# 001_USB.net
KiCad netlist of a schematic drawn in Altium Designer
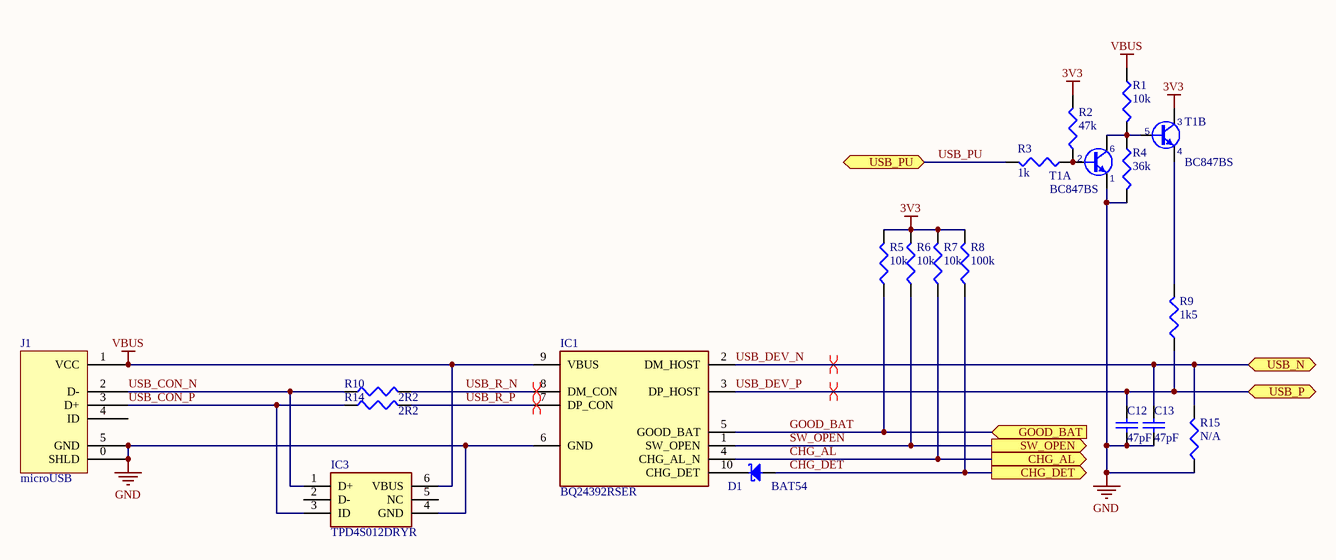
[diagram p0: [001] USB.SchDoc]

(export (version "E")
  (design (tool "Eeschema 10.0.6"))
  (components
    (comp (ref "C12")
      (value "47pF")
      (footprint "1608[0603]")
      (description "Capacitor (Semiconductor SIM Model)")
      (fields (field (name "Comment") "Cap Semi") (field (name "PUBLISHER") "Altium Limited"))
      (libsource (lib "Miscellaneous Devices") (part "Cap Semi"))
    )
    (comp (ref "C13")
      (value "47pF")
      (footprint "1608[0603]")
      (description "Capacitor (Semiconductor SIM Model)")
      (fields (field (name "Comment") "Cap Semi") (field (name "PUBLISHER") "Altium Limited"))
      (libsource (lib "Miscellaneous Devices") (part "Cap Semi"))
    )
    (comp (ref "D1")
      (value "BAT54")
      (footprint "SOT95P240X130-3N")
      (description "Diode Schottky  Anode Pin 1 Cathode Pin 3 (Pas de pin 2)")
      (fields
        (field (name "VOLTAGE") "30V")
        (field (name "POWER") "200mA")
        (field (name "AUTHOR") "CERN DEM JLC")
      )
      (libsource (lib "ICs And Semiconductors") (part "Diode Schottky A1C3"))
    )
    (comp (ref "IC1")
      (value "BQ24392RSER")
      (footprint "SamacSys:RSE(R-PUQFN-N10)")
      (description "Integrated Circuit")
      (fields (field (name "MOUSER PART NUMBER") "595-BQ24392RSER") (field (name "RS PART NUMBER") "8279327"))
      (libsource (lib "SamacSys") (part "BQ24392RSER"))
    )
    (comp (ref "IC3")
      (value "TPD4S012DRYR")
      (footprint "SamacSys:SON50P100X145X60-6N")
      (description "Integrated Circuit")
      (fields (field (name "MOUSER2 PART NUMBER") "595-TPD4S012DRYR"))
      (libsource (lib "SamacSys") (part "TPD4S012DRYR"))
    )
    (comp (ref "J1")
      (value "microUSB")
      (footprint "UB-MC5BR3-SDWP604-4S - custom")
      (description "microUSB connector")
      (libsource (lib "6DOF IMU_ver1") (part "microUSB"))
    )
    (comp (ref "R1")
      (value "10k")
      (footprint "J1-0603")
      (description "Resistor")
      (fields (field (name "Comment") "Res3") (field (name "PUBLISHER") "Altium Limited"))
      (libsource (lib "Miscellaneous Devices") (part "Res3"))
    )
    (comp (ref "R2")
      (value "47k")
      (footprint "J1-0603")
      (description "Resistor")
      (fields (field (name "Comment") "Res3") (field (name "PUBLISHER") "Altium Limited"))
      (libsource (lib "Miscellaneous Devices") (part "Res3"))
    )
    (comp (ref "R3")
      (value "1k")
      (footprint "J1-0603")
      (description "Resistor")
      (fields (field (name "Comment") "Res3") (field (name "PUBLISHER") "Altium Limited"))
      (libsource (lib "Miscellaneous Devices") (part "Res3"))
    )
    (comp (ref "R4")
      (value "36k")
      (footprint "J1-0603")
      (description "Resistor")
      (fields (field (name "Comment") "Res3") (field (name "PUBLISHER") "Altium Limited"))
      (libsource (lib "Miscellaneous Devices") (part "Res3"))
    )
    (comp (ref "R5")
      (value "10k")
      (footprint "J1-0603")
      (description "Resistor")
      (fields (field (name "Comment") "Res3") (field (name "PUBLISHER") "Altium Limited"))
      (libsource (lib "Miscellaneous Devices") (part "Res3"))
    )
    (comp (ref "R6")
      (value "10k")
      (footprint "J1-0603")
      (description "Resistor")
      (fields (field (name "Comment") "Res3") (field (name "PUBLISHER") "Altium Limited"))
      (libsource (lib "Miscellaneous Devices") (part "Res3"))
    )
    (comp (ref "R7")
      (value "10k")
      (footprint "J1-0603")
      (description "Resistor")
      (fields (field (name "Comment") "Res3") (field (name "PUBLISHER") "Altium Limited"))
      (libsource (lib "Miscellaneous Devices") (part "Res3"))
    )
    (comp (ref "R8")
      (value "100k")
      (footprint "J1-0603")
      (description "Resistor")
      (fields (field (name "Comment") "Res3") (field (name "PUBLISHER") "Altium Limited"))
      (libsource (lib "Miscellaneous Devices") (part "Res3"))
    )
    (comp (ref "R9")
      (value "1k5")
      (footprint "J1-0603")
      (description "Resistor")
      (fields (field (name "Comment") "Res3") (field (name "PUBLISHER") "Altium Limited"))
      (libsource (lib "Miscellaneous Devices") (part "Res3"))
    )
    (comp (ref "R10")
      (value "2R2")
      (footprint "J1-0603")
      (description "Resistor")
      (fields (field (name "Comment") "Res3") (field (name "PUBLISHER") "Altium Limited"))
      (libsource (lib "Miscellaneous Devices") (part "Res3"))
    )
    (comp (ref "R14")
      (value "2R2")
      (footprint "J1-0603")
      (description "Resistor")
      (fields (field (name "Comment") "Res3") (field (name "PUBLISHER") "Altium Limited"))
      (libsource (lib "Miscellaneous Devices") (part "Res3"))
    )
    (comp (ref "R15")
      (value "N/A")
      (footprint "J1-0603")
      (description "Resistor")
      (fields (field (name "Comment") "Res3") (field (name "PUBLISHER") "Altium Limited"))
      (libsource (lib "Miscellaneous Devices") (part "Res3"))
    )
    (comp (ref "T1")
      (value "BC847BS")
      (footprint "SOT65P210X110-6N")
      (description "45V 100mA Dual NPN General-Purpose Transistor")
      (fields (field (name "MANUFACTURER") "NXP SEMICONDUCTORS") (field (name "AUTHOR") "CERN DEM JMW"))
      (libsource (lib "ICs And Semiconductors") (part "BC847BS"))
    )
  )
  (nets
    (net (code "1") (name "/CHG_AL") (class "Default")
      (node (ref "IC1") (pin "4") (pinfunction "CHG_AL_N_4") (pintype "passive"))
      (node (ref "R7") (pin "1") (pinfunction "1_1") (pintype "passive"))
    )
    (net (code "2") (name "/CHG_DET") (class "Default")
      (node (ref "D1") (pin "1") (pinfunction "A_1") (pintype "passive"))
      (node (ref "R8") (pin "1") (pinfunction "1_1") (pintype "passive"))
    )
    (net (code "3") (name "/GOOD_BAT") (class "Default")
      (node (ref "IC1") (pin "5") (pinfunction "GOOD_BAT_5") (pintype "passive"))
      (node (ref "R5") (pin "1") (pinfunction "1_1") (pintype "passive"))
    )
    (net (code "4") (name "/SW_OPEN") (class "Default")
      (node (ref "IC1") (pin "1") (pinfunction "SW_OPEN_1") (pintype "passive"))
      (node (ref "R6") (pin "1") (pinfunction "1_1") (pintype "passive"))
    )
    (net (code "5") (name "/USB_CON_N") (class "Default")
      (node (ref "IC3") (pin "1") (pinfunction "D+_1") (pintype "passive"))
      (node (ref "J1") (pin "2") (pinfunction "D-_2") (pintype "passive"))
      (node (ref "R10") (pin "1") (pinfunction "1_1") (pintype "passive"))
    )
    (net (code "6") (name "/USB_CON_P") (class "Default")
      (node (ref "IC3") (pin "3") (pinfunction "ID_3") (pintype "passive"))
      (node (ref "J1") (pin "3") (pinfunction "D+_3") (pintype "passive"))
      (node (ref "R14") (pin "1") (pinfunction "1_1") (pintype "passive"))
    )
    (net (code "7") (name "/USB_DEV_N") (class "Default")
      (node (ref "C13") (pin "1") (pinfunction "1_1") (pintype "passive"))
      (node (ref "IC1") (pin "2") (pinfunction "DM_HOST_2") (pintype "passive"))
      (node (ref "R15") (pin "2") (pinfunction "2_2") (pintype "passive"))
    )
    (net (code "8") (name "/USB_DEV_P") (class "Default")
      (node (ref "C12") (pin "1") (pinfunction "1_1") (pintype "passive"))
      (node (ref "IC1") (pin "3") (pinfunction "DP_HOST_3") (pintype "passive"))
      (node (ref "R9") (pin "1") (pinfunction "1_1") (pintype "passive"))
    )
    (net (code "9") (name "/USB_PU") (class "Default")
      (node (ref "R3") (pin "2") (pinfunction "2_2") (pintype "passive"))
    )
    (net (code "10") (name "/USB_R_N") (class "Default")
      (node (ref "IC1") (pin "8") (pinfunction "DM_CON_8") (pintype "passive"))
      (node (ref "R10") (pin "2") (pinfunction "2_2") (pintype "passive"))
    )
    (net (code "11") (name "/USB_R_P") (class "Default")
      (node (ref "IC1") (pin "7") (pinfunction "DP_CON_7") (pintype "passive"))
      (node (ref "R14") (pin "2") (pinfunction "2_2") (pintype "passive"))
    )
    (net (code "12") (name "3V3") (class "Default")
      (node (ref "R2") (pin "2") (pinfunction "2_2") (pintype "passive"))
      (node (ref "R5") (pin "2") (pinfunction "2_2") (pintype "passive"))
      (node (ref "R6") (pin "2") (pinfunction "2_2") (pintype "passive"))
      (node (ref "R7") (pin "2") (pinfunction "2_2") (pintype "passive"))
      (node (ref "R8") (pin "2") (pinfunction "2_2") (pintype "passive"))
      (node (ref "T1") (pin "3") (pinfunction "C_3") (pintype "passive"))
    )
    (net (code "13") (name "GND") (class "Default")
      (node (ref "C12") (pin "2") (pinfunction "2_2") (pintype "passive"))
      (node (ref "C13") (pin "2") (pinfunction "2_2") (pintype "passive"))
      (node (ref "IC1") (pin "6") (pinfunction "GND_6") (pintype "passive"))
      (node (ref "IC3") (pin "4") (pinfunction "GND_4") (pintype "power_in"))
      (node (ref "J1") (pin "0") (pinfunction "SHLD_0") (pintype "passive"))
      (node (ref "J1") (pin "5") (pinfunction "GND_5") (pintype "power_in"))
      (node (ref "R15") (pin "1") (pinfunction "1_1") (pintype "passive"))
      (node (ref "R4") (pin "2") (pinfunction "2_2") (pintype "passive"))
      (node (ref "T1") (pin "1") (pinfunction "E_1") (pintype "passive"))
    )
    (net (code "14") (name "Net-(D1-C)") (class "Default")
      (node (ref "D1") (pin "3") (pinfunction "C_3") (pintype "passive"))
      (node (ref "IC1") (pin "10") (pinfunction "CHG_DET_10") (pintype "passive"))
    )
    (net (code "15") (name "Net-(T1A-B)") (class "Default")
      (node (ref "R2") (pin "1") (pinfunction "1_1") (pintype "passive"))
      (node (ref "R3") (pin "1") (pinfunction "1_1") (pintype "passive"))
      (node (ref "T1") (pin "2") (pinfunction "B_2") (pintype "passive"))
    )
    (net (code "16") (name "Net-(T1A-C)") (class "Default")
      (node (ref "R1") (pin "2") (pinfunction "2_2") (pintype "passive"))
      (node (ref "R4") (pin "1") (pinfunction "1_1") (pintype "passive"))
      (node (ref "T1") (pin "5") (pinfunction "B_5") (pintype "passive"))
      (node (ref "T1") (pin "6") (pinfunction "C_6") (pintype "passive"))
    )
    (net (code "17") (name "Net-(T1B-E)") (class "Default")
      (node (ref "R9") (pin "2") (pinfunction "2_2") (pintype "passive"))
      (node (ref "T1") (pin "4") (pinfunction "E_4") (pintype "passive"))
    )
    (net (code "18") (name "VBUS") (class "Default")
      (node (ref "IC1") (pin "9") (pinfunction "VBUS_9") (pintype "passive"))
      (node (ref "IC3") (pin "6") (pinfunction "VBUS_6") (pintype "passive"))
      (node (ref "J1") (pin "1") (pinfunction "VCC_1") (pintype "power_in"))
      (node (ref "R1") (pin "1") (pinfunction "1_1") (pintype "passive"))
    )
    (net (code "19") (name "unconnected-(IC3-D--Pad2)") (class "Default")
      (node (ref "IC3") (pin "2") (pinfunction "D-_2") (pintype "passive"))
    )
    (net (code "20") (name "unconnected-(IC3-NC-Pad5)") (class "Default")
      (node (ref "IC3") (pin "5") (pinfunction "NC_5") (pintype "passive"))
    )
    (net (code "21") (name "unconnected-(J1-ID-Pad4)") (class "Default")
      (node (ref "J1") (pin "4") (pinfunction "ID_4") (pintype "passive"))
    )
  )
)
